# Power.net
KiCad netlist of a schematic drawn in Altium Designer
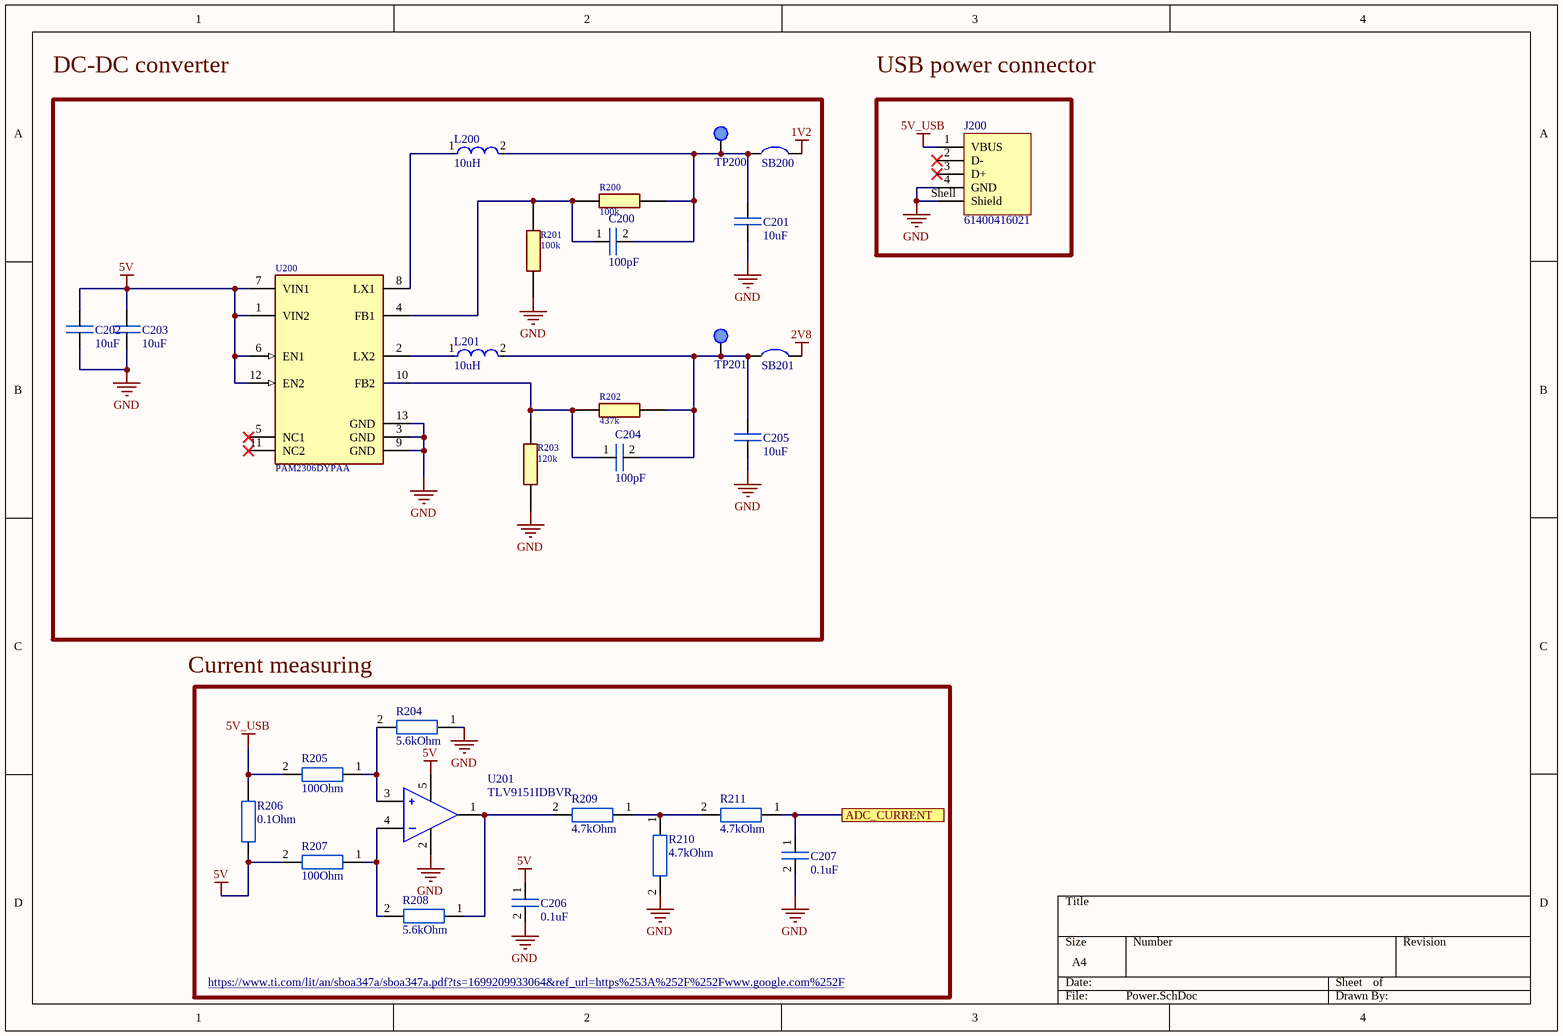
[diagram p0: Power.SchDoc]

(export (version "E")
  (design (tool "Eeschema 10.0.6"))
  (components
    (comp (ref "C200")
      (value "100pF")
      (footprint "0402_footprint")
      (description "0402 capacitor")
      (libsource (lib "Schlib1") (part "Capacitor_0402"))
    )
    (comp (ref "C201")
      (value "10uF")
      (footprint "0805_FOOTPRINT")
      (libsource (lib "Schlib1") (part "Capacitor_0805"))
    )
    (comp (ref "C202")
      (value "10uF")
      (footprint "0805_FOOTPRINT")
      (libsource (lib "Schlib1") (part "Capacitor_0805"))
    )
    (comp (ref "C203")
      (value "10uF")
      (footprint "0805_FOOTPRINT")
      (libsource (lib "Schlib1") (part "Capacitor_0805"))
    )
    (comp (ref "C204")
      (value "100pF")
      (footprint "0402_footprint")
      (description "0402 capacitor")
      (libsource (lib "Schlib1") (part "Capacitor_0402"))
    )
    (comp (ref "C205")
      (value "10uF")
      (footprint "0805_FOOTPRINT")
      (libsource (lib "Schlib1") (part "Capacitor_0805"))
    )
    (comp (ref "C206")
      (value "0.1uF")
      (footprint "0402_footprint")
      (description "0402 capacitor")
      (libsource (lib "Schlib1") (part "Capacitor_0402"))
    )
    (comp (ref "C207")
      (value "0.1uF")
      (footprint "0402_footprint")
      (description "0402 capacitor")
      (libsource (lib "Schlib1") (part "Capacitor_0402"))
    )
    (comp (ref "J200")
      (value "61400416021")
      (footprint "61400416021")
      (libsource (lib "Altium Content Vault") (part "USB 2.0_Type A_Receptacle_1 Port"))
    )
    (comp (ref "L200")
      (value "10uH")
      (footprint "FP-NR5040-H_4_1-MFG")
      (description "SMD Power Inductors 10uH ±20% 2.1A 72.8mΩ")
      (libsource (lib "Altium Content Vault") (part "725321dda6339637d4d059423bc1c3c"))
    )
    (comp (ref "L201")
      (value "10uH")
      (footprint "FP-NR5040-H_4_1-MFG")
      (description "SMD Power Inductors 10uH ±20% 2.1A 72.8mΩ")
      (libsource (lib "Altium Content Vault") (part "725321dda6339637d4d059423bc1c3c"))
    )
    (comp (ref "R200") (value "100k") (footprint "0805") (libsource (lib "Komponent Simbol") (part "R")))
    (comp (ref "R201")
      (value "100k")
      (footprint "0805")
      (description "https://www.mouser.lt/ProductDetail/Panasonic/ERA-6VEB1003V?qs=rI7uf1IzohRHGRtRVKRr%2FA%3D%3D")
      (libsource (lib "") (part "R_2"))
    )
    (comp (ref "R202")
      (value "437k")
      (footprint "0805")
      (description "RN73H2ATTD4373B25")
      (libsource (lib "") (part "R_3"))
    )
    (comp (ref "R203")
      (value "120k")
      (footprint "0805")
      (description "ERA-6AEB124V")
      (libsource (lib "") (part "R_1"))
    )
    (comp (ref "R204")
      (value "5.6kOhm")
      (footprint "0402_footprint")
      (description "0402 resistor")
      (libsource (lib "Schlib1") (part "Resistor_0402"))
    )
    (comp (ref "R205")
      (value "100Ohm")
      (footprint "0402_footprint")
      (description "0402 resistor")
      (libsource (lib "Schlib1") (part "Resistor_0402"))
    )
    (comp (ref "R206")
      (value "0.1Ohm")
      (footprint "0805_FOOTPRINT")
      (libsource (lib "Schlib1") (part "Resistor_0805"))
    )
    (comp (ref "R207")
      (value "100Ohm")
      (footprint "0402_footprint")
      (description "0402 resistor")
      (libsource (lib "Schlib1") (part "Resistor_0402"))
    )
    (comp (ref "R208")
      (value "5.6kOhm")
      (footprint "0402_footprint")
      (description "0402 resistor")
      (libsource (lib "Schlib1") (part "Resistor_0402"))
    )
    (comp (ref "R209")
      (value "4.7kOhm")
      (footprint "0402_footprint")
      (description "0402 resistor")
      (libsource (lib "Schlib1") (part "Resistor_0402"))
    )
    (comp (ref "R210")
      (value "4.7kOhm")
      (footprint "0402_footprint")
      (description "0402 resistor")
      (libsource (lib "Schlib1") (part "Resistor_0402"))
    )
    (comp (ref "R211")
      (value "4.7kOhm")
      (footprint "0402_footprint")
      (description "0402 resistor")
      (libsource (lib "Schlib1") (part "Resistor_0402"))
    )
    (comp (ref "SB200")
      (value "Solder_bridge")
      (footprint "SOLDER_BRIDGE")
      (libsource (lib "Schlib1") (part "Solder_bridge"))
    )
    (comp (ref "SB201")
      (value "Solder_bridge")
      (footprint "SOLDER_BRIDGE")
      (libsource (lib "Schlib1") (part "Solder_bridge"))
    )
    (comp (ref "TP200")
      (value "Test_point")
      (footprint "TEST_POINT")
      (libsource (lib "Schlib1") (part "Test_point"))
    )
    (comp (ref "TP201")
      (value "Test_point")
      (footprint "TEST_POINT")
      (libsource (lib "Schlib1") (part "Test_point"))
    )
    (comp (ref "U200")
      (value "PAM2306DYPAA")
      (footprint "DCDC")
      (libsource (lib "Komponent Simbol") (part "PAM2306DYPAA"))
    )
    (comp (ref "U201")
      (value "TLV9151IDBVR")
      (footprint "FP-DBV0005A-IPC_A")
      (description "OPAMP")
      (libsource (lib "Altium Content Vault") (part "bdbec92199ce4306a818faf70a0ce6e"))
    )
  )
  (nets
    (net (code "1") (name "/ADC_CURRENT") (class "Default")
      (node (ref "C207") (pin "1") (pinfunction "1_1") (pintype "passive"))
      (node (ref "R211") (pin "1") (pinfunction "1_1") (pintype "passive"))
    )
    (net (code "2") (name "1V2") (class "Default")
      (node (ref "SB200") (pin "2") (pinfunction "2_2") (pintype "passive"))
    )
    (net (code "3") (name "2V8") (class "Default")
      (node (ref "SB201") (pin "2") (pinfunction "2_2") (pintype "passive"))
    )
    (net (code "4") (name "5V") (class "Default")
      (node (ref "C202") (pin "2") (pinfunction "2_2") (pintype "passive"))
      (node (ref "C203") (pin "2") (pinfunction "2_2") (pintype "passive"))
      (node (ref "C206") (pin "1") (pinfunction "1_1") (pintype "passive"))
      (node (ref "R206") (pin "1") (pinfunction "1_1") (pintype "passive"))
      (node (ref "R207") (pin "2") (pinfunction "2_2") (pintype "passive"))
      (node (ref "U200") (pin "1") (pinfunction "VIN2_1") (pintype "power_in"))
      (node (ref "U200") (pin "12") (pinfunction "EN2_12") (pintype "input"))
      (node (ref "U200") (pin "6") (pinfunction "EN1_6") (pintype "input"))
      (node (ref "U200") (pin "7") (pinfunction "VIN1_7") (pintype "power_in"))
      (node (ref "U201") (pin "5") (pinfunction "V+_5") (pintype "power_in"))
    )
    (net (code "5") (name "5V_USB") (class "Default")
      (node (ref "J200") (pin "1") (pinfunction "VBUS_1") (pintype "passive"))
      (node (ref "R205") (pin "2") (pinfunction "2_2") (pintype "passive"))
      (node (ref "R206") (pin "2") (pinfunction "2_2") (pintype "passive"))
    )
    (net (code "6") (name "GND") (class "Default")
      (node (ref "C201") (pin "1") (pinfunction "1_1") (pintype "passive"))
      (node (ref "C202") (pin "1") (pinfunction "1_1") (pintype "passive"))
      (node (ref "C203") (pin "1") (pinfunction "1_1") (pintype "passive"))
      (node (ref "C205") (pin "1") (pinfunction "1_1") (pintype "passive"))
      (node (ref "C206") (pin "2") (pinfunction "2_2") (pintype "passive"))
      (node (ref "C207") (pin "2") (pinfunction "2_2") (pintype "passive"))
      (node (ref "J200") (pin "4") (pinfunction "GND_4") (pintype "passive"))
      (node (ref "J200") (pin "Shell") (pinfunction "Shield_Shell") (pintype "passive"))
      (node (ref "R201") (pin "2") (pinfunction "2_2") (pintype "passive"))
      (node (ref "R203") (pin "1") (pinfunction "1_1") (pintype "passive"))
      (node (ref "R204") (pin "1") (pinfunction "1_1") (pintype "passive"))
      (node (ref "R210") (pin "2") (pinfunction "2_2") (pintype "passive"))
      (node (ref "U200") (pin "13") (pinfunction "GND_13") (pintype "power_in"))
      (node (ref "U200") (pin "3") (pinfunction "GND_3") (pintype "power_in"))
      (node (ref "U200") (pin "9") (pinfunction "GND_9") (pintype "power_in"))
      (node (ref "U201") (pin "2") (pinfunction "V-_2") (pintype "power_in"))
    )
    (net (code "7") (name "Net-(C200-Pad2)") (class "Default")
      (node (ref "C200") (pin "2") (pinfunction "2_2") (pintype "passive"))
      (node (ref "C201") (pin "2") (pinfunction "2_2") (pintype "passive"))
      (node (ref "L200") (pin "2") (pinfunction "2_2") (pintype "passive"))
      (node (ref "R200") (pin "2") (pinfunction "2_2") (pintype "passive"))
      (node (ref "SB200") (pin "1") (pinfunction "1_1") (pintype "passive"))
      (node (ref "TP200") (pin "1") (pinfunction "1_1") (pintype "passive"))
    )
    (net (code "8") (name "Net-(C204-Pad2)") (class "Default")
      (node (ref "C204") (pin "2") (pinfunction "2_2") (pintype "passive"))
      (node (ref "C205") (pin "2") (pinfunction "2_2") (pintype "passive"))
      (node (ref "L201") (pin "2") (pinfunction "2_2") (pintype "passive"))
      (node (ref "R202") (pin "1") (pinfunction "1_1") (pintype "passive"))
      (node (ref "SB201") (pin "1") (pinfunction "1_1") (pintype "passive"))
      (node (ref "TP201") (pin "1") (pinfunction "1_1") (pintype "passive"))
    )
    (net (code "9") (name "Net-(R209-Pad1)") (class "Default")
      (node (ref "R209") (pin "1") (pinfunction "1_1") (pintype "passive"))
      (node (ref "R210") (pin "1") (pinfunction "1_1") (pintype "passive"))
      (node (ref "R211") (pin "2") (pinfunction "2_2") (pintype "passive"))
    )
    (net (code "10") (name "Net-(U200-FB1)") (class "Default")
      (node (ref "C200") (pin "1") (pinfunction "1_1") (pintype "passive"))
      (node (ref "R200") (pin "1") (pinfunction "1_1") (pintype "passive"))
      (node (ref "R201") (pin "1") (pinfunction "1_1") (pintype "passive"))
      (node (ref "U200") (pin "4") (pinfunction "FB1_4") (pintype "passive"))
    )
    (net (code "11") (name "Net-(U200-FB2)") (class "Default")
      (node (ref "C204") (pin "1") (pinfunction "1_1") (pintype "passive"))
      (node (ref "R202") (pin "2") (pinfunction "2_2") (pintype "passive"))
      (node (ref "R203") (pin "2") (pinfunction "2_2") (pintype "passive"))
      (node (ref "U200") (pin "10") (pinfunction "FB2_10") (pintype "passive"))
    )
    (net (code "12") (name "Net-(U200-LX1)") (class "Default")
      (node (ref "L200") (pin "1") (pinfunction "1_1") (pintype "passive"))
      (node (ref "U200") (pin "8") (pinfunction "LX1_8") (pintype "passive"))
    )
    (net (code "13") (name "Net-(U200-LX2)") (class "Default")
      (node (ref "L201") (pin "1") (pinfunction "1_1") (pintype "passive"))
      (node (ref "U200") (pin "2") (pinfunction "LX2_2") (pintype "passive"))
    )
    (net (code "14") (name "Net-(U201-IN+)") (class "Default")
      (node (ref "R204") (pin "2") (pinfunction "2_2") (pintype "passive"))
      (node (ref "R205") (pin "1") (pinfunction "1_1") (pintype "passive"))
      (node (ref "U201") (pin "3") (pinfunction "IN+_3") (pintype "tri_state"))
    )
    (net (code "15") (name "Net-(U201-IN-)") (class "Default")
      (node (ref "R207") (pin "1") (pinfunction "1_1") (pintype "passive"))
      (node (ref "R208") (pin "2") (pinfunction "2_2") (pintype "passive"))
      (node (ref "U201") (pin "4") (pinfunction "IN-_4") (pintype "tri_state"))
    )
    (net (code "16") (name "Net-(U201-OUT)") (class "Default")
      (node (ref "R208") (pin "1") (pinfunction "1_1") (pintype "passive"))
      (node (ref "R209") (pin "2") (pinfunction "2_2") (pintype "passive"))
      (node (ref "U201") (pin "1") (pinfunction "OUT_1") (pintype "passive"))
    )
    (net (code "17") (name "unconnected-(J200-D+-Pad3)") (class "Default")
      (node (ref "J200") (pin "3") (pinfunction "D+_3") (pintype "passive+no_connect"))
    )
    (net (code "18") (name "unconnected-(J200-D--Pad2)") (class "Default")
      (node (ref "J200") (pin "2") (pinfunction "D-_2") (pintype "passive+no_connect"))
    )
    (net (code "19") (name "unconnected-(U200-NC1-Pad5)") (class "Default")
      (node (ref "U200") (pin "5") (pinfunction "NC1_5") (pintype "passive+no_connect"))
    )
    (net (code "20") (name "unconnected-(U200-NC2-Pad11)") (class "Default")
      (node (ref "U200") (pin "11") (pinfunction "NC2_11") (pintype "passive+no_connect"))
    )
  )
)
